# design.net
KiCad netlist of a schematic drawn in EasyEDA Pro
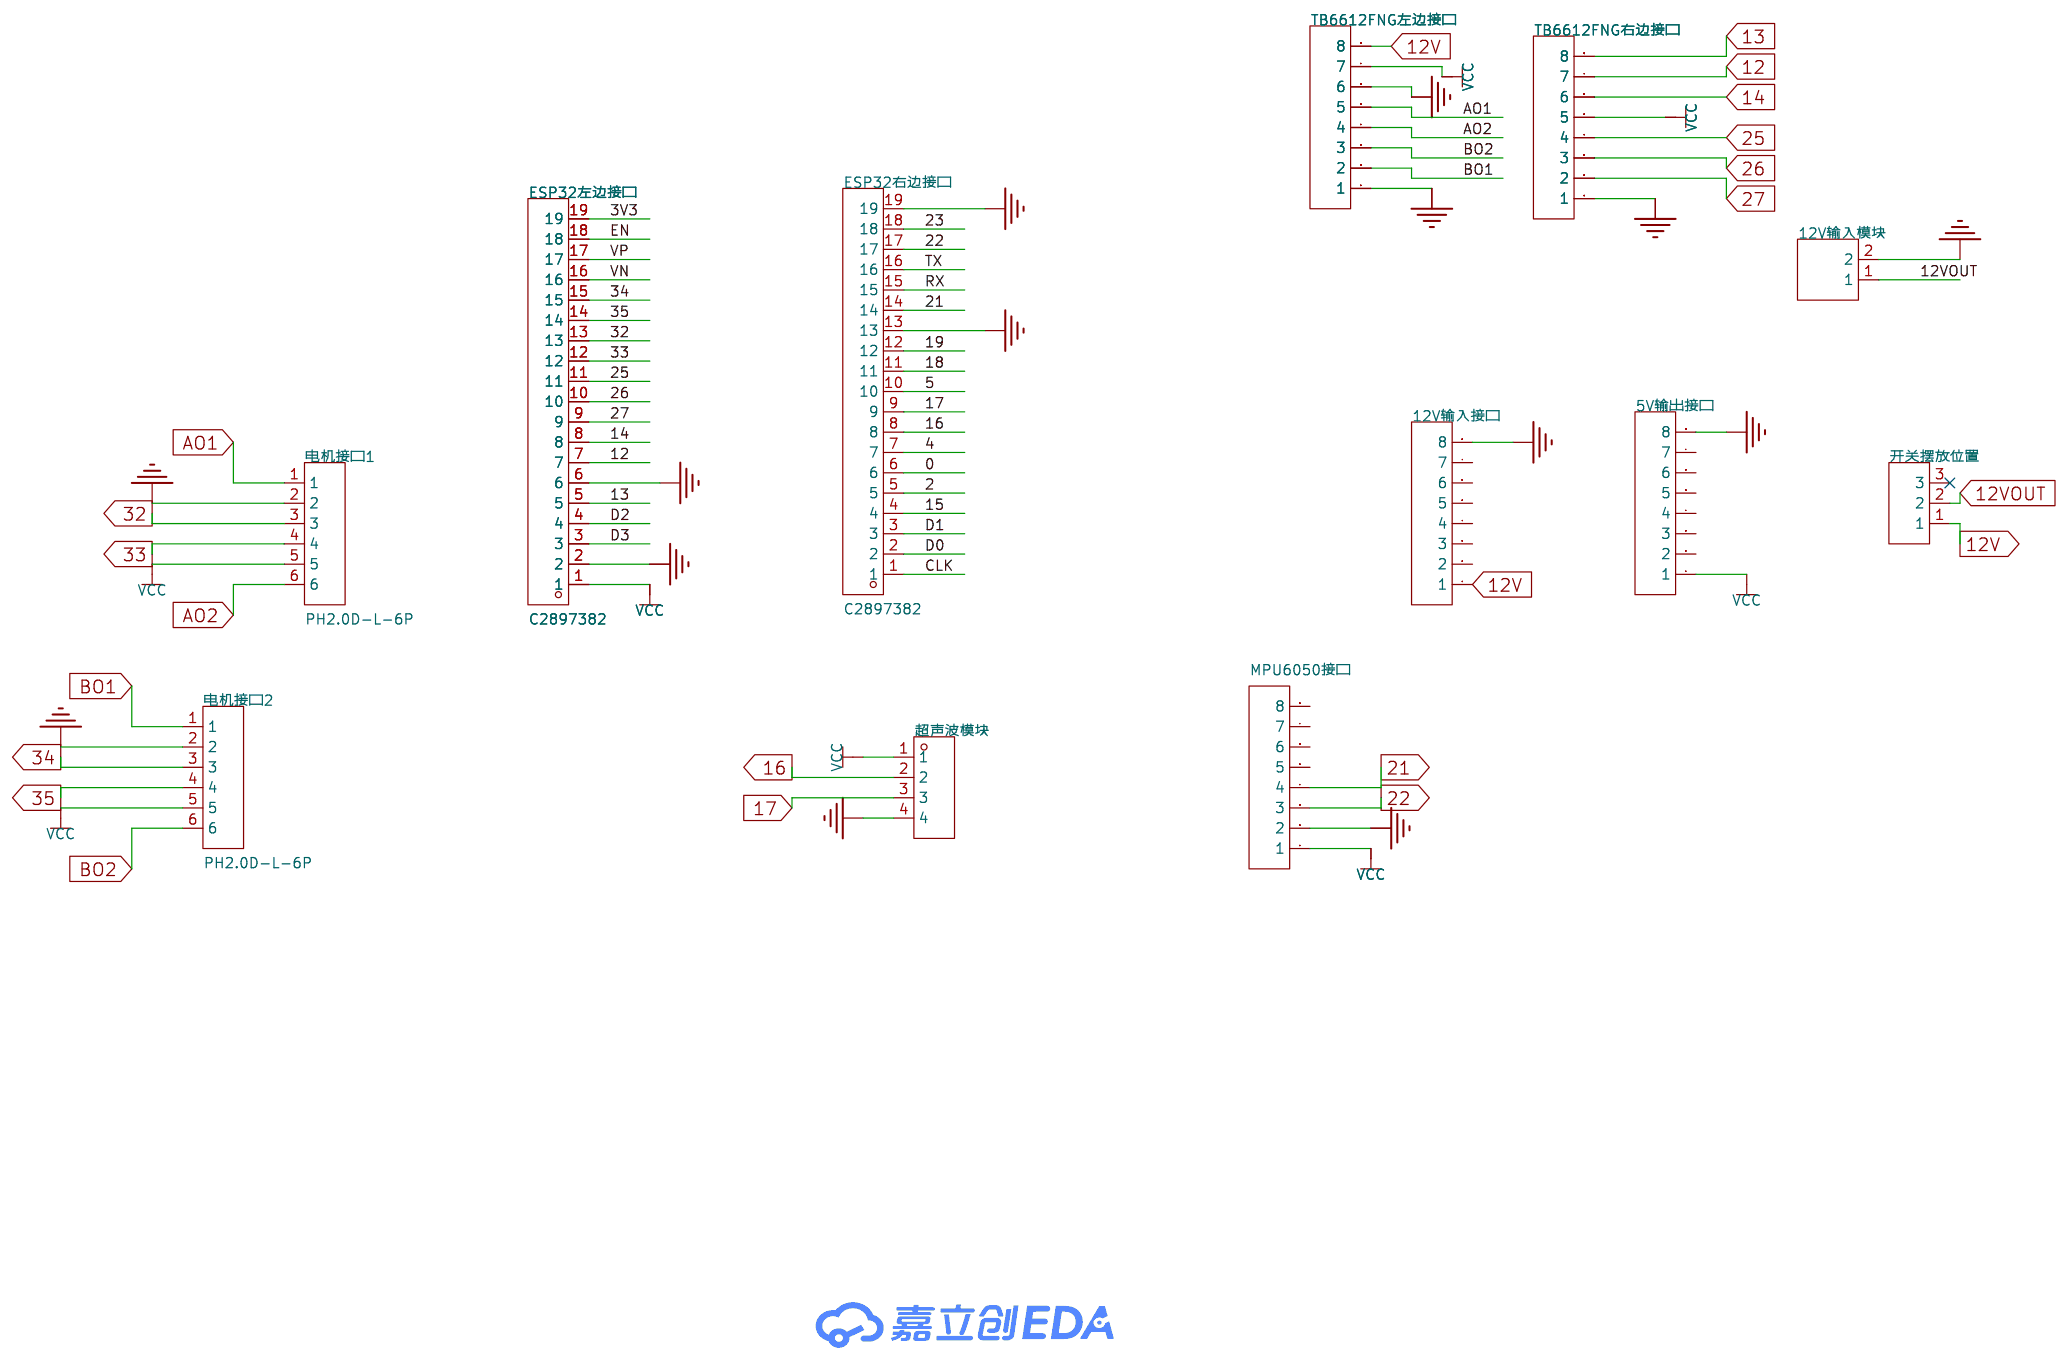
[diagram p0: schematic sheet]

(export (version "E")
  (design (tool "Eeschema 10.0.6"))
  (components
    (comp (ref "5V输出接口")
      (value "~")
      (footprint "easyedapro:HDR-TH_8P-P2.54-V-F-1")
      (libsource (lib "easyedapro") (part "Header-Female-2.54_1x8"))
    )
    (comp (ref "12V输入接口")
      (value "~")
      (footprint "easyedapro:HDR-TH_8P-P2.54-V-F-1")
      (libsource (lib "easyedapro") (part "Header-Female-2.54_1x8"))
    )
    (comp (ref "12V输入模块")
      (value "~")
      (footprint "easyedapro:HDR-TH_2P-P2.54-V-M-1")
      (libsource (lib "easyedapro") (part "210S-1*2P L=11.6MMGold-plated black"))
    )
    (comp (ref "ESP32右边接口")
      (value "C2897382")
      (footprint "easyedapro:HDR-TH_19P-P2.54-V-F")
      (libsource (lib "easyedapro") (part "HDR-F_2.54_1x19P"))
    )
    (comp (ref "ESP32左边接口")
      (value "C2897382")
      (footprint "easyedapro:HDR-TH_19P-P2.54-V-F")
      (libsource (lib "easyedapro") (part "HDR-F_2.54_1x19P"))
    )
    (comp (ref "MPU6050接口")
      (value "~")
      (footprint "easyedapro:HDR-TH_8P-P2.54-V-F-1")
      (libsource (lib "easyedapro") (part "Header-Female-2.54_1x8"))
    )
    (comp (ref "TB6612FNG右边接口")
      (value "~")
      (footprint "easyedapro:HDR-TH_8P-P2.54-V-F-1")
      (libsource (lib "easyedapro") (part "Header-Female-2.54_1x8"))
    )
    (comp (ref "TB6612FNG左边接口")
      (value "~")
      (footprint "easyedapro:HDR-TH_8P-P2.54-V-F-1")
      (libsource (lib "easyedapro") (part "Header-Female-2.54_1x8"))
    )
    (comp (ref "开关摆放位置")
      (value "~")
      (footprint "easyedapro:HDR-TH_3P-P2.54-V-F")
      (libsource (lib "easyedapro") (part "PM254V-11-03-H85"))
    )
    (comp (ref "电机接口1")
      (value "PH2.0D-L-6P")
      (footprint "easyedapro:CONN-TH_6P_PH2.0D-L-6P")
      (libsource (lib "easyedapro") (part "PH2.0D-L-6P"))
    )
    (comp (ref "电机接口2")
      (value "PH2.0D-L-6P")
      (footprint "easyedapro:CONN-TH_6P_PH2.0D-L-6P")
      (libsource (lib "easyedapro") (part "PH2.0D-L-6P"))
    )
    (comp (ref "超声波模块")
      (value "~")
      (footprint "easyedapro:HDR-TH_4P-P2.54-V-F")
      (libsource (lib "easyedapro") (part "2.54-1*4P母"))
    )
  )
  (nets
    (net (code "1") (name "/0") (class "Default")
      (node (ref "ESP32右边接口") (pin "6") (pinfunction "6_6") (pintype "input"))
    )
    (net (code "2") (name "/2") (class "Default")
      (node (ref "ESP32右边接口") (pin "5") (pinfunction "5_5") (pintype "input"))
    )
    (net (code "3") (name "/3V3") (class "Default")
      (node (ref "ESP32左边接口") (pin "19") (pinfunction "19_19") (pintype "input"))
    )
    (net (code "4") (name "/4") (class "Default")
      (node (ref "ESP32右边接口") (pin "7") (pinfunction "7_7") (pintype "input"))
    )
    (net (code "5") (name "/5") (class "Default")
      (node (ref "ESP32右边接口") (pin "10") (pinfunction "10_10") (pintype "input"))
    )
    (net (code "6") (name "/15") (class "Default")
      (node (ref "ESP32右边接口") (pin "4") (pinfunction "4_4") (pintype "input"))
    )
    (net (code "7") (name "/18") (class "Default")
      (node (ref "ESP32右边接口") (pin "11") (pinfunction "11_11") (pintype "input"))
    )
    (net (code "8") (name "/19") (class "Default")
      (node (ref "ESP32右边接口") (pin "12") (pinfunction "12_12") (pintype "input"))
    )
    (net (code "9") (name "/23") (class "Default")
      (node (ref "ESP32右边接口") (pin "18") (pinfunction "18_18") (pintype "input"))
    )
    (net (code "10") (name "/CLK") (class "Default")
      (node (ref "ESP32右边接口") (pin "1") (pinfunction "1_1") (pintype "input"))
    )
    (net (code "11") (name "/D0") (class "Default")
      (node (ref "ESP32右边接口") (pin "2") (pinfunction "2_2") (pintype "input"))
    )
    (net (code "12") (name "/D1") (class "Default")
      (node (ref "ESP32右边接口") (pin "3") (pinfunction "3_3") (pintype "input"))
    )
    (net (code "13") (name "/D2") (class "Default")
      (node (ref "ESP32左边接口") (pin "4") (pinfunction "4_4") (pintype "input"))
    )
    (net (code "14") (name "/D3") (class "Default")
      (node (ref "ESP32左边接口") (pin "3") (pinfunction "3_3") (pintype "input"))
    )
    (net (code "15") (name "/EN") (class "Default")
      (node (ref "ESP32左边接口") (pin "18") (pinfunction "18_18") (pintype "input"))
    )
    (net (code "16") (name "/RX") (class "Default")
      (node (ref "ESP32右边接口") (pin "15") (pinfunction "15_15") (pintype "input"))
    )
    (net (code "17") (name "/TX") (class "Default")
      (node (ref "ESP32右边接口") (pin "16") (pinfunction "16_16") (pintype "input"))
    )
    (net (code "18") (name "/VN") (class "Default")
      (node (ref "ESP32左边接口") (pin "16") (pinfunction "16_16") (pintype "input"))
    )
    (net (code "19") (name "/VP") (class "Default")
      (node (ref "ESP32左边接口") (pin "17") (pinfunction "17_17") (pintype "input"))
    )
    (net (code "20") (name "12") (class "Default")
      (node (ref "ESP32左边接口") (pin "7") (pinfunction "7_7") (pintype "input"))
      (node (ref "TB6612FNG右边接口") (pin "7") (pinfunction "7_7") (pintype "input"))
    )
    (net (code "21") (name "12V") (class "Default")
      (node (ref "12V输入接口") (pin "1") (pinfunction "1_1") (pintype "input"))
      (node (ref "TB6612FNG左边接口") (pin "8") (pinfunction "8_8") (pintype "input"))
      (node (ref "开关摆放位置") (pin "1") (pinfunction "1_1") (pintype "unspecified"))
    )
    (net (code "22") (name "12VOUT") (class "Default")
      (node (ref "12V输入模块") (pin "1") (pinfunction "1_1") (pintype "unspecified"))
      (node (ref "开关摆放位置") (pin "2") (pinfunction "2_2") (pintype "unspecified"))
    )
    (net (code "23") (name "13") (class "Default")
      (node (ref "ESP32左边接口") (pin "5") (pinfunction "5_5") (pintype "input"))
      (node (ref "TB6612FNG右边接口") (pin "8") (pinfunction "8_8") (pintype "input"))
    )
    (net (code "24") (name "14") (class "Default")
      (node (ref "ESP32左边接口") (pin "8") (pinfunction "8_8") (pintype "input"))
      (node (ref "TB6612FNG右边接口") (pin "6") (pinfunction "6_6") (pintype "input"))
    )
    (net (code "25") (name "16") (class "Default")
      (node (ref "ESP32右边接口") (pin "8") (pinfunction "8_8") (pintype "input"))
      (node (ref "超声波模块") (pin "2") (pinfunction "2_2") (pintype "unspecified"))
    )
    (net (code "26") (name "17") (class "Default")
      (node (ref "ESP32右边接口") (pin "9") (pinfunction "9_9") (pintype "input"))
      (node (ref "超声波模块") (pin "3") (pinfunction "3_3") (pintype "unspecified"))
    )
    (net (code "27") (name "21") (class "Default")
      (node (ref "ESP32右边接口") (pin "14") (pinfunction "14_14") (pintype "input"))
      (node (ref "MPU6050接口") (pin "4") (pinfunction "4_4") (pintype "input"))
    )
    (net (code "28") (name "22") (class "Default")
      (node (ref "ESP32右边接口") (pin "17") (pinfunction "17_17") (pintype "input"))
      (node (ref "MPU6050接口") (pin "3") (pinfunction "3_3") (pintype "input"))
    )
    (net (code "29") (name "25") (class "Default")
      (node (ref "ESP32左边接口") (pin "11") (pinfunction "11_11") (pintype "input"))
      (node (ref "TB6612FNG右边接口") (pin "4") (pinfunction "4_4") (pintype "input"))
    )
    (net (code "30") (name "26") (class "Default")
      (node (ref "ESP32左边接口") (pin "10") (pinfunction "10_10") (pintype "input"))
      (node (ref "TB6612FNG右边接口") (pin "3") (pinfunction "3_3") (pintype "input"))
    )
    (net (code "31") (name "27") (class "Default")
      (node (ref "ESP32左边接口") (pin "9") (pinfunction "9_9") (pintype "input"))
      (node (ref "TB6612FNG右边接口") (pin "2") (pinfunction "2_2") (pintype "input"))
    )
    (net (code "32") (name "32") (class "Default")
      (node (ref "ESP32左边接口") (pin "13") (pinfunction "13_13") (pintype "input"))
      (node (ref "电机接口1") (pin "3") (pinfunction "3_3") (pintype "unspecified"))
    )
    (net (code "33") (name "33") (class "Default")
      (node (ref "ESP32左边接口") (pin "12") (pinfunction "12_12") (pintype "input"))
      (node (ref "电机接口1") (pin "4") (pinfunction "4_4") (pintype "unspecified"))
    )
    (net (code "34") (name "34") (class "Default")
      (node (ref "ESP32左边接口") (pin "15") (pinfunction "15_15") (pintype "input"))
      (node (ref "电机接口2") (pin "3") (pinfunction "3_3") (pintype "unspecified"))
    )
    (net (code "35") (name "35") (class "Default")
      (node (ref "ESP32左边接口") (pin "14") (pinfunction "14_14") (pintype "input"))
      (node (ref "电机接口2") (pin "4") (pinfunction "4_4") (pintype "unspecified"))
    )
    (net (code "36") (name "AO1") (class "Default")
      (node (ref "TB6612FNG左边接口") (pin "5") (pinfunction "5_5") (pintype "input"))
      (node (ref "电机接口1") (pin "1") (pinfunction "1_1") (pintype "unspecified"))
    )
    (net (code "37") (name "AO2") (class "Default")
      (node (ref "TB6612FNG左边接口") (pin "4") (pinfunction "4_4") (pintype "input"))
      (node (ref "电机接口1") (pin "6") (pinfunction "6_6") (pintype "unspecified"))
    )
    (net (code "38") (name "BO1") (class "Default")
      (node (ref "TB6612FNG左边接口") (pin "2") (pinfunction "2_2") (pintype "input"))
      (node (ref "电机接口2") (pin "1") (pinfunction "1_1") (pintype "unspecified"))
    )
    (net (code "39") (name "BO2") (class "Default")
      (node (ref "TB6612FNG左边接口") (pin "3") (pinfunction "3_3") (pintype "input"))
      (node (ref "电机接口2") (pin "6") (pinfunction "6_6") (pintype "unspecified"))
    )
    (net (code "40") (name "GND") (class "Default")
      (node (ref "12V输入接口") (pin "8") (pinfunction "8_8") (pintype "input"))
      (node (ref "12V输入模块") (pin "2") (pinfunction "2_2") (pintype "unspecified"))
      (node (ref "5V输出接口") (pin "8") (pinfunction "8_8") (pintype "input"))
      (node (ref "ESP32右边接口") (pin "13") (pinfunction "13_13") (pintype "input"))
      (node (ref "ESP32右边接口") (pin "19") (pinfunction "19_19") (pintype "input"))
      (node (ref "ESP32左边接口") (pin "2") (pinfunction "2_2") (pintype "input"))
      (node (ref "ESP32左边接口") (pin "6") (pinfunction "6_6") (pintype "input"))
      (node (ref "MPU6050接口") (pin "2") (pinfunction "2_2") (pintype "input"))
      (node (ref "TB6612FNG右边接口") (pin "1") (pinfunction "1_1") (pintype "input"))
      (node (ref "TB6612FNG左边接口") (pin "1") (pinfunction "1_1") (pintype "input"))
      (node (ref "TB6612FNG左边接口") (pin "6") (pinfunction "6_6") (pintype "input"))
      (node (ref "电机接口1") (pin "2") (pinfunction "2_2") (pintype "unspecified"))
      (node (ref "电机接口2") (pin "2") (pinfunction "2_2") (pintype "unspecified"))
      (node (ref "超声波模块") (pin "4") (pinfunction "4_4") (pintype "unspecified"))
    )
    (net (code "41") (name "VCC") (class "Default")
      (node (ref "5V输出接口") (pin "1") (pinfunction "1_1") (pintype "input"))
      (node (ref "ESP32左边接口") (pin "1") (pinfunction "1_1") (pintype "input"))
      (node (ref "MPU6050接口") (pin "1") (pinfunction "1_1") (pintype "input"))
      (node (ref "TB6612FNG右边接口") (pin "5") (pinfunction "5_5") (pintype "input"))
      (node (ref "TB6612FNG左边接口") (pin "7") (pinfunction "7_7") (pintype "input"))
      (node (ref "电机接口1") (pin "5") (pinfunction "5_5") (pintype "unspecified"))
      (node (ref "电机接口2") (pin "5") (pinfunction "5_5") (pintype "unspecified"))
      (node (ref "超声波模块") (pin "1") (pinfunction "1_1") (pintype "unspecified"))
    )
    (net (code "42") (name "unconnected-(5V输出接口-Pad2)") (class "Default")
      (node (ref "5V输出接口") (pin "2") (pinfunction "2_2") (pintype "input"))
    )
    (net (code "43") (name "unconnected-(5V输出接口-Pad3)") (class "Default")
      (node (ref "5V输出接口") (pin "3") (pinfunction "3_3") (pintype "input"))
    )
    (net (code "44") (name "unconnected-(5V输出接口-Pad4)") (class "Default")
      (node (ref "5V输出接口") (pin "4") (pinfunction "4_4") (pintype "input"))
    )
    (net (code "45") (name "unconnected-(5V输出接口-Pad5)") (class "Default")
      (node (ref "5V输出接口") (pin "5") (pinfunction "5_5") (pintype "input"))
    )
    (net (code "46") (name "unconnected-(5V输出接口-Pad6)") (class "Default")
      (node (ref "5V输出接口") (pin "6") (pinfunction "6_6") (pintype "input"))
    )
    (net (code "47") (name "unconnected-(5V输出接口-Pad7)") (class "Default")
      (node (ref "5V输出接口") (pin "7") (pinfunction "7_7") (pintype "input"))
    )
    (net (code "48") (name "unconnected-(12V输入接口-Pad2)") (class "Default")
      (node (ref "12V输入接口") (pin "2") (pinfunction "2_2") (pintype "input"))
    )
    (net (code "49") (name "unconnected-(12V输入接口-Pad3)") (class "Default")
      (node (ref "12V输入接口") (pin "3") (pinfunction "3_3") (pintype "input"))
    )
    (net (code "50") (name "unconnected-(12V输入接口-Pad4)") (class "Default")
      (node (ref "12V输入接口") (pin "4") (pinfunction "4_4") (pintype "input"))
    )
    (net (code "51") (name "unconnected-(12V输入接口-Pad5)") (class "Default")
      (node (ref "12V输入接口") (pin "5") (pinfunction "5_5") (pintype "input"))
    )
    (net (code "52") (name "unconnected-(12V输入接口-Pad6)") (class "Default")
      (node (ref "12V输入接口") (pin "6") (pinfunction "6_6") (pintype "input"))
    )
    (net (code "53") (name "unconnected-(12V输入接口-Pad7)") (class "Default")
      (node (ref "12V输入接口") (pin "7") (pinfunction "7_7") (pintype "input"))
    )
    (net (code "54") (name "unconnected-(MPU6050接口-Pad5)") (class "Default")
      (node (ref "MPU6050接口") (pin "5") (pinfunction "5_5") (pintype "input"))
    )
    (net (code "55") (name "unconnected-(MPU6050接口-Pad6)") (class "Default")
      (node (ref "MPU6050接口") (pin "6") (pinfunction "6_6") (pintype "input"))
    )
    (net (code "56") (name "unconnected-(MPU6050接口-Pad7)") (class "Default")
      (node (ref "MPU6050接口") (pin "7") (pinfunction "7_7") (pintype "input"))
    )
    (net (code "57") (name "unconnected-(MPU6050接口-Pad8)") (class "Default")
      (node (ref "MPU6050接口") (pin "8") (pinfunction "8_8") (pintype "input"))
    )
    (net (code "58") (name "unconnected-(开关摆放位置-Pad3)") (class "Default")
      (node (ref "开关摆放位置") (pin "3") (pinfunction "3_3") (pintype "unspecified+no_connect"))
    )
  )
)
